# SparkFun_Qwiic_Buzzer.net
KiCad netlist of a schematic drawn in EAGLE
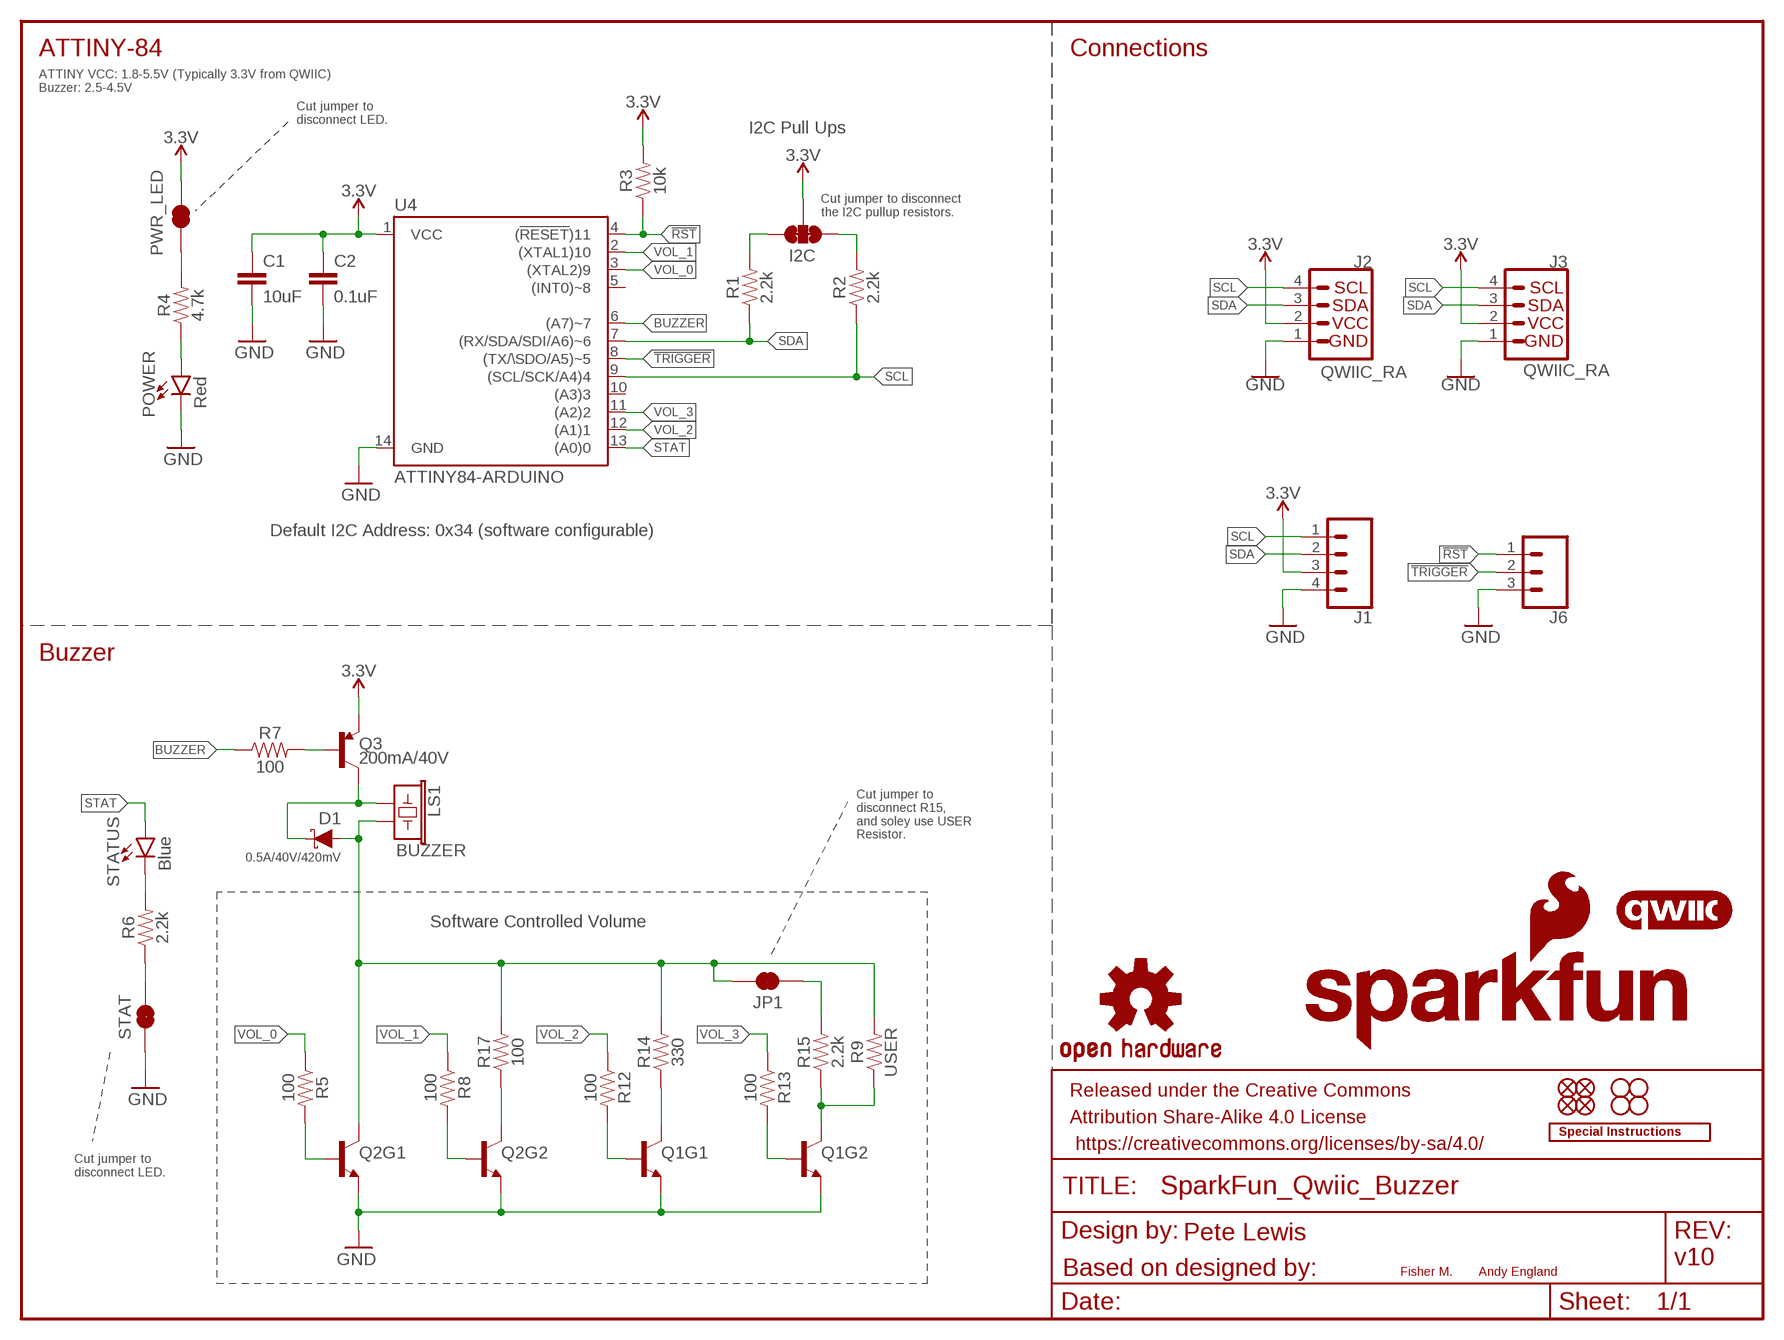
[diagram p0: schematic, sheet 1]

(export (version "E")
  (design (tool "Eeschema 10.0.6"))
  (components
    (comp (ref "C1")
      (value "10uF")
      (footprint "eagle-import:0402-TIGHT")
      (libsource (lib "eagle-import") (part "10UF-0402T-6.3V-20%"))
    )
    (comp (ref "C2")
      (value "0.1uF")
      (footprint "eagle-import:0402-TIGHT")
      (libsource (lib "eagle-import") (part "0.1UF-0402T-16V-10%"))
    )
    (comp (ref "D1")
      (value "0.5A/40V/420mV")
      (footprint "eagle-import:SOD-323")
      (libsource (lib "eagle-import") (part "DIODE-SCHOTTKY-PMEG4005EJ"))
    )
    (comp (ref "FRAME1")
      (value "FRAME-LETTER")
      (footprint "eagle-import:CREATIVE_COMMONS")
      (libsource (lib "eagle-import") (part "FRAME-LETTER"))
    )
    (comp (ref "H1")
      (value "STAND-OFF")
      (footprint "eagle-import:STAND-OFF")
      (libsource (lib "eagle-import") (part "STAND-OFF"))
    )
    (comp (ref "H2")
      (value "STAND-OFF")
      (footprint "eagle-import:STAND-OFF")
      (libsource (lib "eagle-import") (part "STAND-OFF"))
    )
    (comp (ref "H3")
      (value "STAND-OFF")
      (footprint "eagle-import:STAND-OFF")
      (libsource (lib "eagle-import") (part "STAND-OFF"))
    )
    (comp (ref "H4")
      (value "STAND-OFF")
      (footprint "eagle-import:STAND-OFF")
      (libsource (lib "eagle-import") (part "STAND-OFF"))
    )
    (comp (ref "I2C")
      (value "JUMPER-SMT_3_2-NC_TRACE_SILK")
      (footprint "eagle-import:SMT-JUMPER_3_2-NC_TRACE_SILK")
      (libsource (lib "eagle-import") (part "JUMPER-SMT_3_2-NC_TRACE_SILK"))
    )
    (comp (ref "J1")
      (value "CONN_041X04_NO_SILK")
      (footprint "eagle-import:1X04_NO_SILK")
      (libsource (lib "eagle-import") (part "CONN_041X04_NO_SILK"))
    )
    (comp (ref "J2")
      (value "QWIIC_RA")
      (footprint "eagle-import:JST04_1MM_RA")
      (libsource (lib "eagle-import") (part "QWIIC_CONNECTORJS-1MM"))
    )
    (comp (ref "J3")
      (value "QWIIC_RA")
      (footprint "eagle-import:JST04_1MM_RA")
      (libsource (lib "eagle-import") (part "QWIIC_CONNECTORJS-1MM"))
    )
    (comp (ref "J6")
      (value "CONN_031X03_NO_SILK")
      (footprint "eagle-import:1X03_NO_SILK")
      (libsource (lib "eagle-import") (part "CONN_031X03_NO_SILK"))
    )
    (comp (ref "JP1")
      (value "JUMPER-SMT_2_NC_TRACE_SILK")
      (footprint "eagle-import:SMT-JUMPER_2_NC_TRACE_SILK")
      (libsource (lib "eagle-import") (part "JUMPER-SMT_2_NC_TRACE_SILK"))
    )
    (comp (ref "JP2")
      (value "FIDUCIALUFIDUCIAL")
      (footprint "eagle-import:FIDUCIAL-MICRO")
      (libsource (lib "eagle-import") (part "FIDUCIALUFIDUCIAL"))
    )
    (comp (ref "JP6")
      (value "FIDUCIALUFIDUCIAL")
      (footprint "eagle-import:FIDUCIAL-MICRO")
      (libsource (lib "eagle-import") (part "FIDUCIALUFIDUCIAL"))
    )
    (comp (ref "JP8")
      (value "FIDUCIALUFIDUCIAL")
      (footprint "eagle-import:FIDUCIAL-MICRO")
      (libsource (lib "eagle-import") (part "FIDUCIALUFIDUCIAL"))
    )
    (comp (ref "JP9")
      (value "FIDUCIALUFIDUCIAL")
      (footprint "eagle-import:FIDUCIAL-MICRO")
      (libsource (lib "eagle-import") (part "FIDUCIALUFIDUCIAL"))
    )
    (comp (ref "LOGO1")
      (value "OSHW-LOGOMINI")
      (footprint "eagle-import:OSHW-LOGO-MINI")
      (libsource (lib "eagle-import") (part "OSHW-LOGOMINI"))
    )
    (comp (ref "LOGO2")
      (value "SFE_LOGO_NAME_FLAME.1_INCH")
      (footprint "eagle-import:SFE_LOGO_NAME_FLAME_.1")
      (libsource (lib "eagle-import") (part "SFE_LOGO_NAME_FLAME.1_INCH"))
    )
    (comp (ref "LOGO3")
      (value "SPECIAL_INSTRUCTIONS-ORDERING")
      (footprint "eagle-import:ORDERING_INSTRUCTIONS")
      (libsource (lib "eagle-import") (part "SPECIAL_INSTRUCTIONS-ORDERING"))
    )
    (comp (ref "LOGO4")
      (value "SFE_LOGO_FLAME.1_INCH")
      (footprint "eagle-import:SFE_LOGO_FLAME_.1")
      (libsource (lib "eagle-import") (part "SFE_LOGO_FLAME.1_INCH"))
    )
    (comp (ref "LOGO5")
      (value "QWIIC_LOGO_4MM")
      (footprint "eagle-import:QWIIC_4MM")
      (libsource (lib "eagle-import") (part "QWIIC_LOGO_4MM"))
    )
    (comp (ref "LS1")
      (value "BUZZER")
      (footprint "eagle-import:BUZZER-CCV")
      (libsource (lib "eagle-import") (part "BUZZER-SMD"))
    )
    (comp (ref "POWER")
      (value "Red")
      (footprint "eagle-import:LED-0603")
      (libsource (lib "eagle-import") (part "LED-RED_0603-KB"))
    )
    (comp (ref "PWR_LED")
      (value "PWR_LED")
      (footprint "eagle-import:SMT-JUMPER_2_NC_TRACE_SILK")
      (libsource (lib "eagle-import") (part "JUMPER-SMT_2_NC_TRACE_SILK"))
    )
    (comp (ref "Q1")
      (value "TRANS_NPN_DUAL-MBT3904DW1T1")
      (footprint "eagle-import:SC70-6")
      (libsource (lib "eagle-import") (part "TRANS_NPN_DUAL-MBT3904DW1T1"))
    )
    (comp (ref "Q2")
      (value "TRANS_NPN_DUAL-MBT3904DW1T1")
      (footprint "eagle-import:SC70-6")
      (libsource (lib "eagle-import") (part "TRANS_NPN_DUAL-MBT3904DW1T1"))
    )
    (comp (ref "Q3")
      (value "200mA/40V")
      (footprint "eagle-import:SOT23-3")
      (libsource (lib "eagle-import") (part "TRANS_PNP-PMBT3906|MMBT3906L"))
    )
    (comp (ref "R1")
      (value "2.2k")
      (footprint "eagle-import:0402-TIGHT")
      (libsource (lib "eagle-import") (part "2.2KOHM-0402T-1/16W-1%"))
    )
    (comp (ref "R2")
      (value "2.2k")
      (footprint "eagle-import:0402-TIGHT")
      (libsource (lib "eagle-import") (part "2.2KOHM-0402T-1/16W-1%"))
    )
    (comp (ref "R3")
      (value "10k")
      (footprint "eagle-import:0402-TIGHT")
      (libsource (lib "eagle-import") (part "10KOHM-0402T-1/16W-1%"))
    )
    (comp (ref "R4")
      (value "4.7k")
      (footprint "eagle-import:0402-TIGHT")
      (libsource (lib "eagle-import") (part "4.7KOHM-0402T-1/16W-1%"))
    )
    (comp (ref "R5")
      (value "100")
      (footprint "eagle-import:0402-TIGHT")
      (libsource (lib "eagle-import") (part "100OHM-0402-TIGHT-1/16W-1%"))
    )
    (comp (ref "R6")
      (value "2.2k")
      (footprint "eagle-import:0402-TIGHT")
      (libsource (lib "eagle-import") (part "2.2KOHM-0402T-1/16W-1%"))
    )
    (comp (ref "R7")
      (value "100")
      (footprint "eagle-import:0402-TIGHT")
      (libsource (lib "eagle-import") (part "100OHM-0402-TIGHT-1/16W-1%"))
    )
    (comp (ref "R8")
      (value "100")
      (footprint "eagle-import:0402-TIGHT")
      (libsource (lib "eagle-import") (part "100OHM-0402-TIGHT-1/16W-1%"))
    )
    (comp (ref "R9")
      (value "USER")
      (footprint "eagle-import:AXIAL-0.3")
      (libsource (lib "eagle-import") (part "RESISTORAXIAL-0.3"))
    )
    (comp (ref "R12")
      (value "100")
      (footprint "eagle-import:0402-TIGHT")
      (libsource (lib "eagle-import") (part "100OHM-0402-TIGHT-1/16W-1%"))
    )
    (comp (ref "R13")
      (value "100")
      (footprint "eagle-import:0402-TIGHT")
      (libsource (lib "eagle-import") (part "100OHM-0402-TIGHT-1/16W-1%"))
    )
    (comp (ref "R14")
      (value "330")
      (footprint "eagle-import:0402-TIGHT")
      (libsource (lib "eagle-import") (part "330OHM-0402T-1/16W-5%"))
    )
    (comp (ref "R15")
      (value "2.2k")
      (footprint "eagle-import:0402-TIGHT")
      (libsource (lib "eagle-import") (part "2.2KOHM-0402T-1/16W-1%"))
    )
    (comp (ref "R17")
      (value "100")
      (footprint "eagle-import:0402-TIGHT")
      (libsource (lib "eagle-import") (part "100OHM-0402-TIGHT-1/16W-1%"))
    )
    (comp (ref "STAT")
      (value "PWR_LED")
      (footprint "eagle-import:SMT-JUMPER_2_NC_TRACE_SILK")
      (libsource (lib "eagle-import") (part "JUMPER-SMT_2_NC_TRACE_SILK"))
    )
    (comp (ref "STATUS")
      (value "Blue")
      (footprint "eagle-import:LED-0603")
      (libsource (lib "eagle-import") (part "LED-BLUE0603"))
    )
    (comp (ref "U4")
      (value "ATTINY84-ARDUINO")
      (footprint "eagle-import:SO14")
      (libsource (lib "eagle-import") (part "ATTINY84-ARDUINO"))
    )
  )
  (nets
    (net (code "1") (name "/~{RST}") (class "Default")
      (node (ref "J6") (pin "1") (pinfunction "1_1") (pintype "passive"))
      (node (ref "R3") (pin "1") (pinfunction "1_1") (pintype "passive"))
      (node (ref "U4") (pin "4") (pinfunction "(~{RESET})11_4") (pintype "bidirectional"))
    )
    (net (code "2") (name "/~{TRIGGER}") (class "Default")
      (node (ref "J6") (pin "2") (pinfunction "2_2") (pintype "passive"))
      (node (ref "U4") (pin "8") (pinfunction "(TX/\\SDO/A5)~{5}_8") (pintype "bidirectional"))
    )
    (net (code "3") (name "3.3V") (class "Default")
      (node (ref "C1") (pin "1") (pinfunction "1_1") (pintype "passive"))
      (node (ref "C2") (pin "1") (pinfunction "1_1") (pintype "passive"))
      (node (ref "I2C") (pin "2") (pinfunction "2_2") (pintype "passive"))
      (node (ref "J1") (pin "3") (pinfunction "3_3") (pintype "passive"))
      (node (ref "J2") (pin "2") (pinfunction "2_2") (pintype "power_in"))
      (node (ref "J3") (pin "2") (pinfunction "2_2") (pintype "power_in"))
      (node (ref "PWR_LED") (pin "2") (pinfunction "2_2") (pintype "passive"))
      (node (ref "Q3") (pin "2") (pinfunction "E_2") (pintype "passive"))
      (node (ref "R3") (pin "2") (pinfunction "2_2") (pintype "passive"))
      (node (ref "U4") (pin "1") (pinfunction "VCC_1") (pintype "bidirectional"))
    )
    (net (code "4") (name "BUZZER") (class "Default")
      (node (ref "R7") (pin "1") (pinfunction "1_1") (pintype "passive"))
      (node (ref "U4") (pin "6") (pinfunction "(A7)~{7}_6") (pintype "bidirectional"))
    )
    (net (code "5") (name "GND") (class "Default")
      (node (ref "C1") (pin "2") (pinfunction "2_2") (pintype "passive"))
      (node (ref "C2") (pin "2") (pinfunction "2_2") (pintype "passive"))
      (node (ref "J1") (pin "4") (pinfunction "4_4") (pintype "passive"))
      (node (ref "J2") (pin "1") (pinfunction "1_1") (pintype "power_in"))
      (node (ref "J3") (pin "1") (pinfunction "1_1") (pintype "power_in"))
      (node (ref "J6") (pin "3") (pinfunction "3_3") (pintype "passive"))
      (node (ref "POWER") (pin "C") (pinfunction "C_C") (pintype "passive"))
      (node (ref "Q1") (pin "1") (pinfunction "E_1") (pintype "passive"))
      (node (ref "Q1") (pin "4") (pinfunction "E_4") (pintype "passive"))
      (node (ref "Q2") (pin "1") (pinfunction "E_1") (pintype "passive"))
      (node (ref "Q2") (pin "4") (pinfunction "E_4") (pintype "passive"))
      (node (ref "STAT") (pin "1") (pinfunction "1_1") (pintype "passive"))
      (node (ref "U4") (pin "14") (pinfunction "GND_14") (pintype "bidirectional"))
    )
    (net (code "6") (name "Net-(I2C-Pad1)") (class "Default")
      (node (ref "I2C") (pin "1") (pinfunction "1_1") (pintype "passive"))
      (node (ref "R2") (pin "2") (pinfunction "2_2") (pintype "passive"))
    )
    (net (code "7") (name "Net-(I2C-Pad3)") (class "Default")
      (node (ref "I2C") (pin "3") (pinfunction "3_3") (pintype "passive"))
      (node (ref "R1") (pin "2") (pinfunction "2_2") (pintype "passive"))
    )
    (net (code "8") (name "Net-(JP1-Pad1)") (class "Default")
      (node (ref "JP1") (pin "1") (pinfunction "1_1") (pintype "passive"))
      (node (ref "R15") (pin "2") (pinfunction "2_2") (pintype "passive"))
    )
    (net (code "9") (name "Net-(LS1-1)") (class "Default")
      (node (ref "D1") (pin "C") (pinfunction "C_C") (pintype "passive"))
      (node (ref "LS1") (pin "+") (pinfunction "1_+") (pintype "passive"))
      (node (ref "Q3") (pin "3") (pinfunction "C_3") (pintype "passive"))
    )
    (net (code "10") (name "Net-(LS1-2)") (class "Default")
      (node (ref "D1") (pin "A") (pinfunction "A_A") (pintype "passive"))
      (node (ref "JP1") (pin "2") (pinfunction "2_2") (pintype "passive"))
      (node (ref "LS1") (pin "-") (pinfunction "2_-") (pintype "passive"))
      (node (ref "Q2") (pin "3") (pinfunction "C_3") (pintype "passive"))
      (node (ref "R14") (pin "2") (pinfunction "2_2") (pintype "passive"))
      (node (ref "R17") (pin "2") (pinfunction "2_2") (pintype "passive"))
      (node (ref "R9") (pin "P$2") (pinfunction "2_P$2") (pintype "passive"))
    )
    (net (code "11") (name "Net-(POWER-PadA)") (class "Default")
      (node (ref "POWER") (pin "A") (pinfunction "A_A") (pintype "passive"))
      (node (ref "R4") (pin "1") (pinfunction "1_1") (pintype "passive"))
    )
    (net (code "12") (name "Net-(PWR_LED-Pad1)") (class "Default")
      (node (ref "PWR_LED") (pin "1") (pinfunction "1_1") (pintype "passive"))
      (node (ref "R4") (pin "2") (pinfunction "2_2") (pintype "passive"))
    )
    (net (code "13") (name "Net-(Q1A-B)") (class "Default")
      (node (ref "Q1") (pin "5") (pinfunction "B_5") (pintype "passive"))
      (node (ref "R12") (pin "2") (pinfunction "2_2") (pintype "passive"))
    )
    (net (code "14") (name "Net-(Q1A-C)") (class "Default")
      (node (ref "Q1") (pin "3") (pinfunction "C_3") (pintype "passive"))
      (node (ref "R14") (pin "1") (pinfunction "1_1") (pintype "passive"))
    )
    (net (code "15") (name "Net-(Q1B-B)") (class "Default")
      (node (ref "Q1") (pin "2") (pinfunction "B_2") (pintype "passive"))
      (node (ref "R13") (pin "2") (pinfunction "2_2") (pintype "passive"))
    )
    (net (code "16") (name "Net-(Q1B-C)") (class "Default")
      (node (ref "Q1") (pin "6") (pinfunction "C_6") (pintype "passive"))
      (node (ref "R15") (pin "1") (pinfunction "1_1") (pintype "passive"))
      (node (ref "R9") (pin "P$1") (pinfunction "1_P$1") (pintype "passive"))
    )
    (net (code "17") (name "Net-(Q2A-B)") (class "Default")
      (node (ref "Q2") (pin "5") (pinfunction "B_5") (pintype "passive"))
      (node (ref "R5") (pin "2") (pinfunction "2_2") (pintype "passive"))
    )
    (net (code "18") (name "Net-(Q2B-B)") (class "Default")
      (node (ref "Q2") (pin "2") (pinfunction "B_2") (pintype "passive"))
      (node (ref "R8") (pin "2") (pinfunction "2_2") (pintype "passive"))
    )
    (net (code "19") (name "Net-(Q2B-C)") (class "Default")
      (node (ref "Q2") (pin "6") (pinfunction "C_6") (pintype "passive"))
      (node (ref "R17") (pin "1") (pinfunction "1_1") (pintype "passive"))
    )
    (net (code "20") (name "Net-(Q3-B)") (class "Default")
      (node (ref "Q3") (pin "1") (pinfunction "B_1") (pintype "passive"))
      (node (ref "R7") (pin "2") (pinfunction "2_2") (pintype "passive"))
    )
    (net (code "21") (name "Net-(R6-Pad1)") (class "Default")
      (node (ref "R6") (pin "1") (pinfunction "1_1") (pintype "passive"))
      (node (ref "STAT") (pin "2") (pinfunction "2_2") (pintype "passive"))
    )
    (net (code "22") (name "Net-(R6-Pad2)") (class "Default")
      (node (ref "R6") (pin "2") (pinfunction "2_2") (pintype "passive"))
      (node (ref "STATUS") (pin "C") (pinfunction "C_C") (pintype "passive"))
    )
    (net (code "23") (name "SCL") (class "Default")
      (node (ref "J1") (pin "1") (pinfunction "1_1") (pintype "passive"))
      (node (ref "J2") (pin "4") (pinfunction "4_4") (pintype "passive"))
      (node (ref "J3") (pin "4") (pinfunction "4_4") (pintype "passive"))
      (node (ref "R2") (pin "1") (pinfunction "1_1") (pintype "passive"))
      (node (ref "U4") (pin "9") (pinfunction "(SCL/SCK/A4)4_9") (pintype "bidirectional"))
    )
    (net (code "24") (name "SDA") (class "Default")
      (node (ref "J1") (pin "2") (pinfunction "2_2") (pintype "passive"))
      (node (ref "J2") (pin "3") (pinfunction "3_3") (pintype "passive"))
      (node (ref "J3") (pin "3") (pinfunction "3_3") (pintype "passive"))
      (node (ref "R1") (pin "1") (pinfunction "1_1") (pintype "passive"))
      (node (ref "U4") (pin "7") (pinfunction "(RX/SDA/SDI/A6)~{6}_7") (pintype "bidirectional"))
    )
    (net (code "25") (name "STAT") (class "Default")
      (node (ref "STATUS") (pin "A") (pinfunction "A_A") (pintype "passive"))
      (node (ref "U4") (pin "13") (pinfunction "(A0)0_13") (pintype "bidirectional"))
    )
    (net (code "26") (name "VOL_0") (class "Default")
      (node (ref "R5") (pin "1") (pinfunction "1_1") (pintype "passive"))
      (node (ref "U4") (pin "3") (pinfunction "(XTAL2)9_3") (pintype "bidirectional"))
    )
    (net (code "27") (name "VOL_1") (class "Default")
      (node (ref "R8") (pin "1") (pinfunction "1_1") (pintype "passive"))
      (node (ref "U4") (pin "2") (pinfunction "(XTAL1)10_2") (pintype "bidirectional"))
    )
    (net (code "28") (name "VOL_2") (class "Default")
      (node (ref "R12") (pin "1") (pinfunction "1_1") (pintype "passive"))
      (node (ref "U4") (pin "12") (pinfunction "(A1)1_12") (pintype "bidirectional"))
    )
    (net (code "29") (name "VOL_3") (class "Default")
      (node (ref "R13") (pin "1") (pinfunction "1_1") (pintype "passive"))
      (node (ref "U4") (pin "11") (pinfunction "(A2)2_11") (pintype "bidirectional"))
    )
    (net (code "30") (name "unconnected-(U4-(A3)3-Pad10)") (class "Default")
      (node (ref "U4") (pin "10") (pinfunction "(A3)3_10") (pintype "bidirectional"))
    )
    (net (code "31") (name "unconnected-(U4-(INT0)~{8}-Pad5)") (class "Default")
      (node (ref "U4") (pin "5") (pinfunction "(INT0)~{8}_5") (pintype "bidirectional"))
    )
  )
)
